# 51_board.net
KiCad netlist of a schematic drawn in Altium Designer
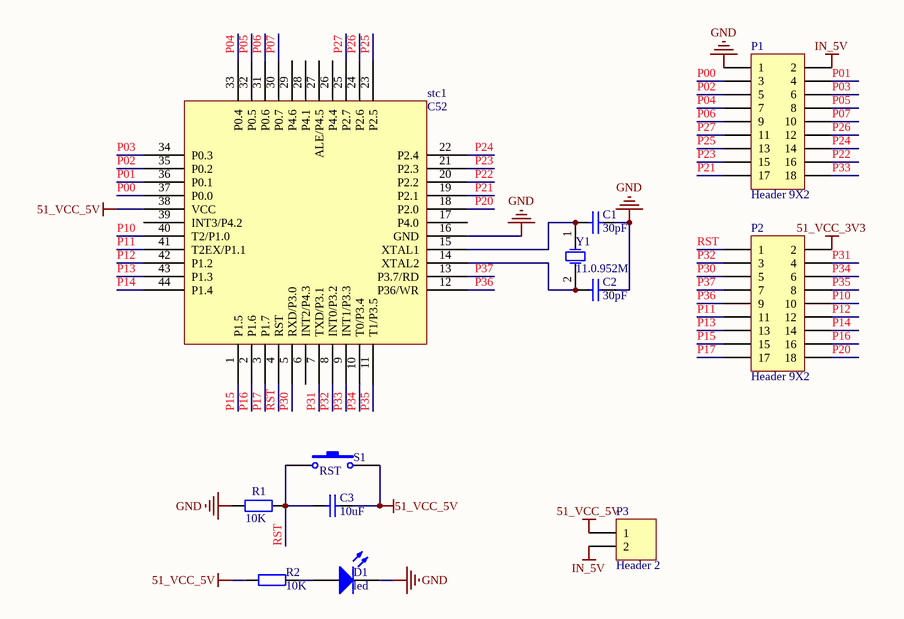
[diagram p0: 51_board.SchDoc]

(export (version "E")
  (design (tool "Eeschema 10.0.6"))
  (components
    (comp (ref "C1")
      (value "30pF")
      (footprint "6-0805_N")
      (description "Capacitor")
      (fields (field (name "PUBLISHER") "Altium Limited"))
      (libsource (lib "Miscellaneous Devices") (part "Cap"))
    )
    (comp (ref "C2")
      (value "30pF")
      (footprint "6-0805_N")
      (description "Capacitor")
      (fields (field (name "PUBLISHER") "Altium Limited"))
      (libsource (lib "Miscellaneous Devices") (part "Cap"))
    )
    (comp (ref "C3")
      (value "10uF")
      (footprint "6-0805_N")
      (description "Capacitor")
      (fields (field (name "PUBLISHER") "Altium Limited"))
      (libsource (lib "Miscellaneous Devices") (part "Cap"))
    )
    (comp (ref "D1")
      (value "led")
      (footprint "LED")
      (description "Typical INFRARED GaAs LED")
      (fields (field (name "PUBLISHER") "Altium Limited"))
      (libsource (lib "Miscellaneous Devices") (part "LED0"))
    )
    (comp (ref "P1")
      (value "Header 9X2")
      (footprint "XDR2x9_S")
      (description "Header, 9-Pin, Dual row")
      (fields (field (name "PUBLISHER") "Altium Limited"))
      (libsource (lib "Miscellaneous Connectors") (part "Header 9X2"))
    )
    (comp (ref "P2")
      (value "Header 9X2")
      (footprint "XDR2x9_S")
      (description "Header, 9-Pin, Dual row")
      (fields (field (name "PUBLISHER") "Altium Limited"))
      (libsource (lib "Miscellaneous Connectors") (part "Header 9X2"))
    )
    (comp (ref "P3")
      (value "Header 2")
      (footprint "HDR1X2")
      (description "Header, 2-Pin")
      (fields (field (name "PUBLISHER") "Altium Limited"))
      (libsource (lib "Miscellaneous Connectors") (part "Header 2"))
    )
    (comp (ref "R1")
      (value "10K")
      (footprint "6-0805_N")
      (description "Resistor")
      (fields (field (name "PUBLISHER") "Altium Limited"))
      (libsource (lib "Miscellaneous Devices") (part "Res2"))
    )
    (comp (ref "R2")
      (value "10K")
      (footprint "6-0805_N")
      (description "Resistor")
      (fields (field (name "PUBLISHER") "Altium Limited"))
      (libsource (lib "Miscellaneous Devices") (part "Res2"))
    )
    (comp (ref "S1")
      (value "RST")
      (footprint "SPST-2")
      (description "Switch")
      (fields (field (name "PUBLISHER") "Altium Limited"))
      (libsource (lib "Miscellaneous Devices") (part "SW-PB"))
    )
    (comp (ref "stc1") (value "C52") (footprint "LQFP44") (libsource (lib "Schlib1") (part "C52")))
    (comp (ref "Y1")
      (value "11.0.952M")
      (footprint "HC-49S")
      (description "Crystal Oscillator")
      (fields (field (name "PUBLISHER") "Altium Limited"))
      (libsource (lib "Miscellaneous Devices") (part "XTAL"))
    )
  )
  (nets
    (net (code "1") (name "/P00") (class "Default")
      (node (ref "P1") (pin "3") (pinfunction "3_3") (pintype "passive"))
      (node (ref "stc1") (pin "37") (pinfunction "P0.0_37") (pintype "passive"))
    )
    (net (code "2") (name "/P01") (class "Default")
      (node (ref "P1") (pin "4") (pinfunction "4_4") (pintype "passive"))
      (node (ref "stc1") (pin "36") (pinfunction "P0.1_36") (pintype "passive"))
    )
    (net (code "3") (name "/P02") (class "Default")
      (node (ref "P1") (pin "5") (pinfunction "5_5") (pintype "passive"))
      (node (ref "stc1") (pin "35") (pinfunction "P0.2_35") (pintype "passive"))
    )
    (net (code "4") (name "/P03") (class "Default")
      (node (ref "P1") (pin "6") (pinfunction "6_6") (pintype "passive"))
      (node (ref "stc1") (pin "34") (pinfunction "P0.3_34") (pintype "passive"))
    )
    (net (code "5") (name "/P04") (class "Default")
      (node (ref "P1") (pin "7") (pinfunction "7_7") (pintype "passive"))
      (node (ref "stc1") (pin "33") (pinfunction "P0.4_33") (pintype "passive"))
    )
    (net (code "6") (name "/P05") (class "Default")
      (node (ref "P1") (pin "8") (pinfunction "8_8") (pintype "passive"))
      (node (ref "stc1") (pin "32") (pinfunction "P0.5_32") (pintype "passive"))
    )
    (net (code "7") (name "/P06") (class "Default")
      (node (ref "P1") (pin "9") (pinfunction "9_9") (pintype "passive"))
      (node (ref "stc1") (pin "31") (pinfunction "P0.6_31") (pintype "passive"))
    )
    (net (code "8") (name "/P07") (class "Default")
      (node (ref "P1") (pin "10") (pinfunction "10_10") (pintype "passive"))
      (node (ref "stc1") (pin "30") (pinfunction "P0.7_30") (pintype "passive"))
    )
    (net (code "9") (name "/P10") (class "Default")
      (node (ref "P2") (pin "10") (pinfunction "10_10") (pintype "passive"))
      (node (ref "stc1") (pin "40") (pinfunction "T2/P1.0_40") (pintype "passive"))
    )
    (net (code "10") (name "/P11") (class "Default")
      (node (ref "P2") (pin "11") (pinfunction "11_11") (pintype "passive"))
      (node (ref "stc1") (pin "41") (pinfunction "T2EX/P1.1_41") (pintype "passive"))
    )
    (net (code "11") (name "/P12") (class "Default")
      (node (ref "P2") (pin "12") (pinfunction "12_12") (pintype "passive"))
      (node (ref "stc1") (pin "42") (pinfunction "P1.2_42") (pintype "passive"))
    )
    (net (code "12") (name "/P13") (class "Default")
      (node (ref "P2") (pin "13") (pinfunction "13_13") (pintype "passive"))
      (node (ref "stc1") (pin "43") (pinfunction "P1.3_43") (pintype "passive"))
    )
    (net (code "13") (name "/P14") (class "Default")
      (node (ref "P2") (pin "14") (pinfunction "14_14") (pintype "passive"))
      (node (ref "stc1") (pin "44") (pinfunction "P1.4_44") (pintype "passive"))
    )
    (net (code "14") (name "/P15") (class "Default")
      (node (ref "P2") (pin "15") (pinfunction "15_15") (pintype "passive"))
      (node (ref "stc1") (pin "1") (pinfunction "P1.5_1") (pintype "passive"))
    )
    (net (code "15") (name "/P16") (class "Default")
      (node (ref "P2") (pin "16") (pinfunction "16_16") (pintype "passive"))
      (node (ref "stc1") (pin "2") (pinfunction "P1.6_2") (pintype "passive"))
    )
    (net (code "16") (name "/P17") (class "Default")
      (node (ref "P2") (pin "17") (pinfunction "17_17") (pintype "passive"))
      (node (ref "stc1") (pin "3") (pinfunction "P1.7_3") (pintype "passive"))
    )
    (net (code "17") (name "/P20") (class "Default")
      (node (ref "P2") (pin "18") (pinfunction "18_18") (pintype "passive"))
      (node (ref "stc1") (pin "18") (pinfunction "P2.0_18") (pintype "passive"))
    )
    (net (code "18") (name "/P21") (class "Default")
      (node (ref "P1") (pin "17") (pinfunction "17_17") (pintype "passive"))
      (node (ref "stc1") (pin "19") (pinfunction "P2.1_19") (pintype "passive"))
    )
    (net (code "19") (name "/P22") (class "Default")
      (node (ref "P1") (pin "16") (pinfunction "16_16") (pintype "passive"))
      (node (ref "stc1") (pin "20") (pinfunction "P2.2_20") (pintype "passive"))
    )
    (net (code "20") (name "/P23") (class "Default")
      (node (ref "P1") (pin "15") (pinfunction "15_15") (pintype "passive"))
      (node (ref "stc1") (pin "21") (pinfunction "P2.3_21") (pintype "passive"))
    )
    (net (code "21") (name "/P24") (class "Default")
      (node (ref "P1") (pin "14") (pinfunction "14_14") (pintype "passive"))
      (node (ref "stc1") (pin "22") (pinfunction "P2.4_22") (pintype "passive"))
    )
    (net (code "22") (name "/P25") (class "Default")
      (node (ref "P1") (pin "13") (pinfunction "13_13") (pintype "passive"))
      (node (ref "stc1") (pin "23") (pinfunction "P2.5_23") (pintype "passive"))
    )
    (net (code "23") (name "/P26") (class "Default")
      (node (ref "P1") (pin "12") (pinfunction "12_12") (pintype "passive"))
      (node (ref "stc1") (pin "24") (pinfunction "P2.6_24") (pintype "passive"))
    )
    (net (code "24") (name "/P27") (class "Default")
      (node (ref "P1") (pin "11") (pinfunction "11_11") (pintype "passive"))
      (node (ref "stc1") (pin "25") (pinfunction "P2.7_25") (pintype "passive"))
    )
    (net (code "25") (name "/P30") (class "Default")
      (node (ref "P2") (pin "5") (pinfunction "5_5") (pintype "passive"))
      (node (ref "stc1") (pin "5") (pinfunction "RXD/P3.0_5") (pintype "passive"))
    )
    (net (code "26") (name "/P31") (class "Default")
      (node (ref "P2") (pin "4") (pinfunction "4_4") (pintype "passive"))
      (node (ref "stc1") (pin "7") (pinfunction "TXD/P3.1_7") (pintype "passive"))
    )
    (net (code "27") (name "/P32") (class "Default")
      (node (ref "P2") (pin "3") (pinfunction "3_3") (pintype "passive"))
      (node (ref "stc1") (pin "8") (pinfunction "INT0/P3.2_8") (pintype "passive"))
    )
    (net (code "28") (name "/P33") (class "Default")
      (node (ref "P1") (pin "18") (pinfunction "18_18") (pintype "passive"))
      (node (ref "stc1") (pin "9") (pinfunction "INT1/P3.3_9") (pintype "passive"))
    )
    (net (code "29") (name "/P34") (class "Default")
      (node (ref "P2") (pin "6") (pinfunction "6_6") (pintype "passive"))
      (node (ref "stc1") (pin "10") (pinfunction "T0/P3.4_10") (pintype "passive"))
    )
    (net (code "30") (name "/P35") (class "Default")
      (node (ref "P2") (pin "8") (pinfunction "8_8") (pintype "passive"))
      (node (ref "stc1") (pin "11") (pinfunction "T1/P3.5_11") (pintype "passive"))
    )
    (net (code "31") (name "/P36") (class "Default")
      (node (ref "P2") (pin "9") (pinfunction "9_9") (pintype "passive"))
      (node (ref "stc1") (pin "12") (pinfunction "P36/WR_12") (pintype "passive"))
    )
    (net (code "32") (name "/P37") (class "Default")
      (node (ref "P2") (pin "7") (pinfunction "7_7") (pintype "passive"))
      (node (ref "stc1") (pin "13") (pinfunction "P3.7/RD_13") (pintype "passive"))
    )
    (net (code "33") (name "/RST") (class "Default")
      (node (ref "C3") (pin "1") (pinfunction "1_1") (pintype "passive"))
      (node (ref "P2") (pin "1") (pinfunction "1_1") (pintype "passive"))
      (node (ref "R1") (pin "2") (pinfunction "2_2") (pintype "passive"))
      (node (ref "S1") (pin "1") (pinfunction "1_1") (pintype "passive"))
      (node (ref "stc1") (pin "4") (pinfunction "RST_4") (pintype "passive"))
    )
    (net (code "34") (name "51_VCC_3V3") (class "Default")
      (node (ref "P2") (pin "2") (pinfunction "2_2") (pintype "passive"))
    )
    (net (code "35") (name "51_VCC_5V") (class "Default")
      (node (ref "C3") (pin "2") (pinfunction "2_2") (pintype "passive"))
      (node (ref "P3") (pin "1") (pinfunction "1_1") (pintype "passive"))
      (node (ref "R2") (pin "1") (pinfunction "1_1") (pintype "passive"))
      (node (ref "S1") (pin "2") (pinfunction "2_2") (pintype "passive"))
      (node (ref "stc1") (pin "38") (pinfunction "VCC_38") (pintype "passive"))
    )
    (net (code "36") (name "GND") (class "Default")
      (node (ref "C1") (pin "1") (pinfunction "1_1") (pintype "passive"))
      (node (ref "C2") (pin "1") (pinfunction "1_1") (pintype "passive"))
      (node (ref "D1") (pin "2") (pinfunction "K_2") (pintype "passive"))
      (node (ref "P1") (pin "1") (pinfunction "1_1") (pintype "passive"))
      (node (ref "R1") (pin "1") (pinfunction "1_1") (pintype "passive"))
      (node (ref "stc1") (pin "16") (pinfunction "GND_16") (pintype "passive"))
    )
    (net (code "37") (name "IN_5V") (class "Default")
      (node (ref "P1") (pin "2") (pinfunction "2_2") (pintype "passive"))
      (node (ref "P3") (pin "2") (pinfunction "2_2") (pintype "passive"))
    )
    (net (code "38") (name "Net-(D1-A)") (class "Default")
      (node (ref "D1") (pin "1") (pinfunction "A_1") (pintype "passive"))
      (node (ref "R2") (pin "2") (pinfunction "2_2") (pintype "passive"))
    )
    (net (code "39") (name "Net-(Y1-OSC1)") (class "Default")
      (node (ref "C1") (pin "2") (pinfunction "2_2") (pintype "passive"))
      (node (ref "Y1") (pin "1") (pinfunction "OSC1_1") (pintype "passive"))
      (node (ref "stc1") (pin "15") (pinfunction "XTAL1_15") (pintype "passive"))
    )
    (net (code "40") (name "Net-(Y1-OSC2)") (class "Default")
      (node (ref "C2") (pin "2") (pinfunction "2_2") (pintype "passive"))
      (node (ref "Y1") (pin "2") (pinfunction "OSC2_2") (pintype "passive"))
      (node (ref "stc1") (pin "14") (pinfunction "XTAL2_14") (pintype "passive"))
    )
    (net (code "41") (name "unconnected-(stc1-ALE{slash}P4.5-Pad27)") (class "Default")
      (node (ref "stc1") (pin "27") (pinfunction "ALE/P4.5_27") (pintype "passive"))
    )
    (net (code "42") (name "unconnected-(stc1-INT2{slash}P4.3-Pad6)") (class "Default")
      (node (ref "stc1") (pin "6") (pinfunction "INT2/P4.3_6") (pintype "passive"))
    )
    (net (code "43") (name "unconnected-(stc1-INT3{slash}P4.2-Pad39)") (class "Default")
      (node (ref "stc1") (pin "39") (pinfunction "INT3/P4.2_39") (pintype "passive"))
    )
    (net (code "44") (name "unconnected-(stc1-P4.0-Pad17)") (class "Default")
      (node (ref "stc1") (pin "17") (pinfunction "P4.0_17") (pintype "passive"))
    )
    (net (code "45") (name "unconnected-(stc1-P4.1-Pad28)") (class "Default")
      (node (ref "stc1") (pin "28") (pinfunction "P4.1_28") (pintype "passive"))
    )
    (net (code "46") (name "unconnected-(stc1-P4.4-Pad26)") (class "Default")
      (node (ref "stc1") (pin "26") (pinfunction "P4.4_26") (pintype "passive"))
    )
    (net (code "47") (name "unconnected-(stc1-P4.6-Pad29)") (class "Default")
      (node (ref "stc1") (pin "29") (pinfunction "P4.6_29") (pintype "passive"))
    )
  )
)
